# SCH.net
KiCad netlist of a schematic drawn in EAGLE
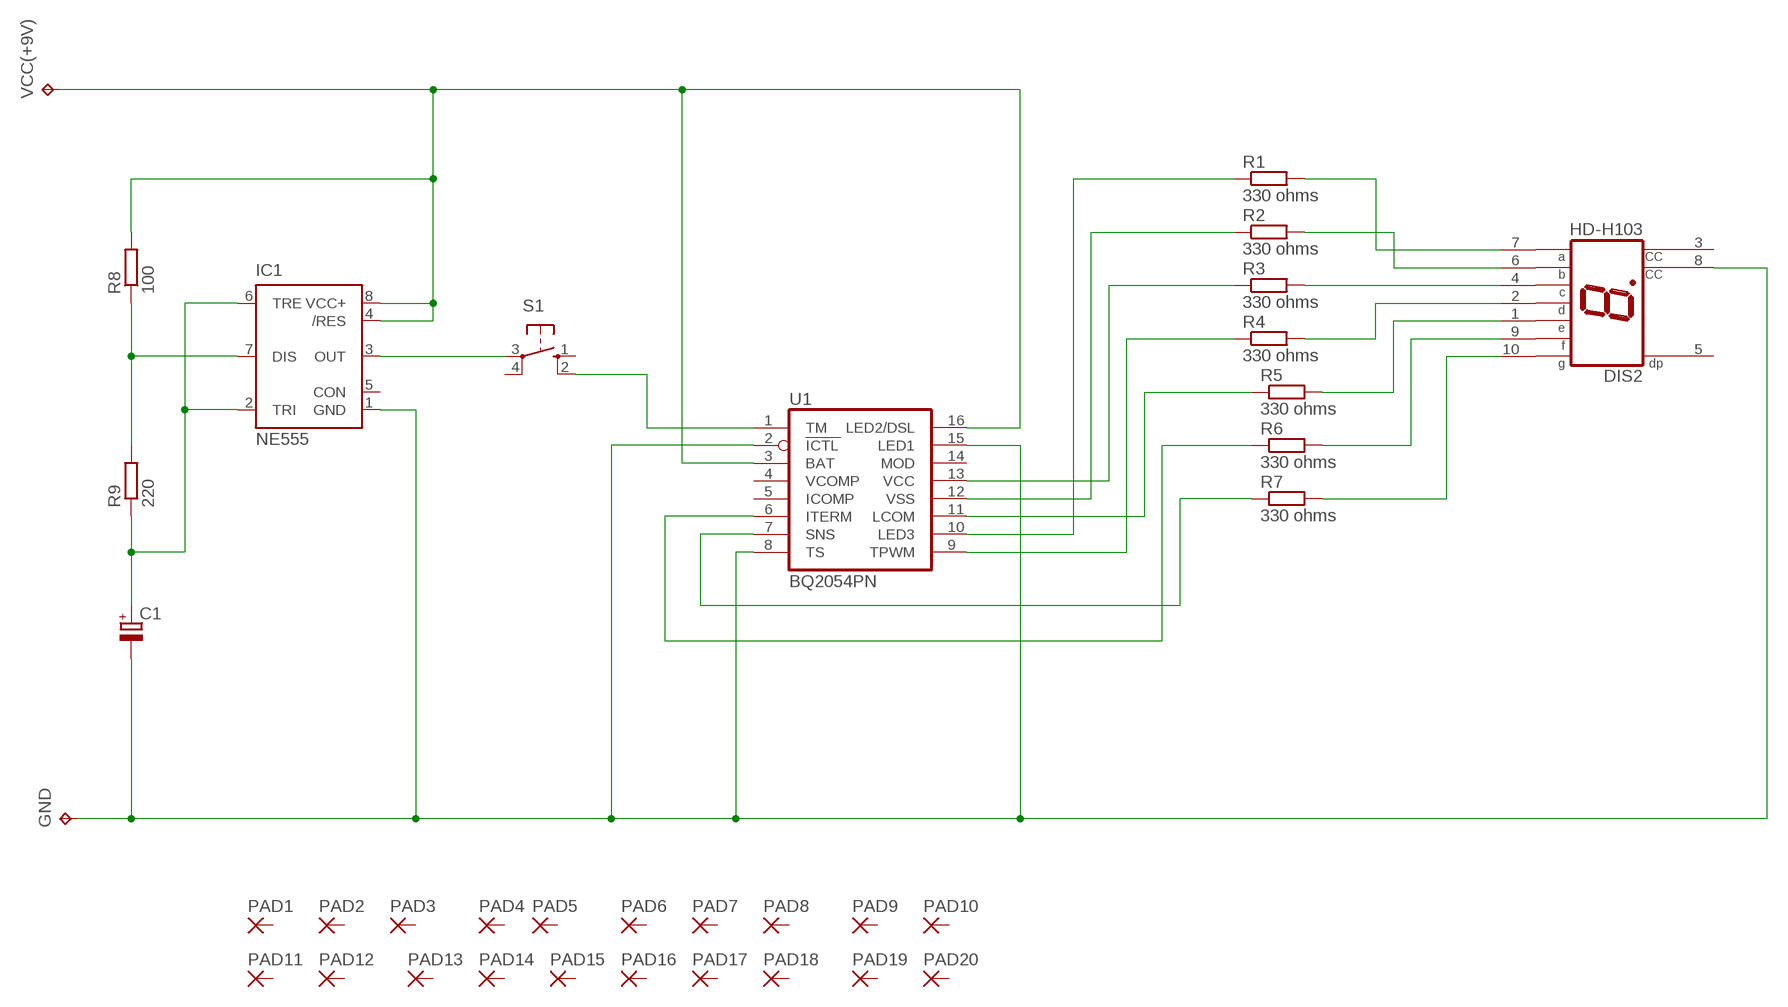
[diagram p0: schematic, sheet 1]

(export (version "E")
  (design (tool "Eeschema 10.0.6"))
  (components
    (comp (ref "C1")
      (value "CPOL-EUB45181B")
      (footprint "eagle-import:B45181B")
      (libsource (lib "eagle-import") (part "CPOL-EUB45181B"))
    )
    (comp (ref "DIS2")
      (value "HD-H103")
      (footprint "eagle-import:HDSP-M")
      (libsource (lib "eagle-import") (part "HD-H103"))
    )
    (comp (ref "GND")
      (value "TPPAD1-13Y")
      (footprint "eagle-import:P1-13Y")
      (libsource (lib "eagle-import") (part "TPPAD1-13Y"))
    )
    (comp (ref "IC1")
      (value "NE555")
      (footprint "eagle-import:DIL-08")
      (fields (field (name "MF") "Arrow Electronics") (field (name "MPN") "NE555N"))
      (libsource (lib "eagle-import") (part "NE555"))
    )
    (comp (ref "PAD1")
      (value "2,54/0,8")
      (footprint "eagle-import:2,54_0,8")
      (libsource (lib "eagle-import") (part "2,54/0,8"))
    )
    (comp (ref "PAD2")
      (value "2,54/0,8")
      (footprint "eagle-import:2,54_0,8")
      (libsource (lib "eagle-import") (part "2,54/0,8"))
    )
    (comp (ref "PAD3")
      (value "2,54/0,8")
      (footprint "eagle-import:2,54_0,8")
      (libsource (lib "eagle-import") (part "2,54/0,8"))
    )
    (comp (ref "PAD4")
      (value "2,54/0,8")
      (footprint "eagle-import:2,54_0,8")
      (libsource (lib "eagle-import") (part "2,54/0,8"))
    )
    (comp (ref "PAD5")
      (value "2,54/0,8")
      (footprint "eagle-import:2,54_0,8")
      (libsource (lib "eagle-import") (part "2,54/0,8"))
    )
    (comp (ref "PAD6")
      (value "2,54/0,8")
      (footprint "eagle-import:2,54_0,8")
      (libsource (lib "eagle-import") (part "2,54/0,8"))
    )
    (comp (ref "PAD7")
      (value "2,54/0,8")
      (footprint "eagle-import:2,54_0,8")
      (libsource (lib "eagle-import") (part "2,54/0,8"))
    )
    (comp (ref "PAD8")
      (value "2,54/0,8")
      (footprint "eagle-import:2,54_0,8")
      (libsource (lib "eagle-import") (part "2,54/0,8"))
    )
    (comp (ref "PAD9")
      (value "2,54/0,8")
      (footprint "eagle-import:2,54_0,8")
      (libsource (lib "eagle-import") (part "2,54/0,8"))
    )
    (comp (ref "PAD10")
      (value "2,54/0,8")
      (footprint "eagle-import:2,54_0,8")
      (libsource (lib "eagle-import") (part "2,54/0,8"))
    )
    (comp (ref "PAD11")
      (value "2,54/0,8")
      (footprint "eagle-import:2,54_0,8")
      (libsource (lib "eagle-import") (part "2,54/0,8"))
    )
    (comp (ref "PAD12")
      (value "2,54/0,8")
      (footprint "eagle-import:2,54_0,8")
      (libsource (lib "eagle-import") (part "2,54/0,8"))
    )
    (comp (ref "PAD13")
      (value "2,54/0,8")
      (footprint "eagle-import:2,54_0,8")
      (libsource (lib "eagle-import") (part "2,54/0,8"))
    )
    (comp (ref "PAD14")
      (value "2,54/0,8")
      (footprint "eagle-import:2,54_0,8")
      (libsource (lib "eagle-import") (part "2,54/0,8"))
    )
    (comp (ref "PAD15")
      (value "2,54/0,8")
      (footprint "eagle-import:2,54_0,8")
      (libsource (lib "eagle-import") (part "2,54/0,8"))
    )
    (comp (ref "PAD16")
      (value "2,54/0,8")
      (footprint "eagle-import:2,54_0,8")
      (libsource (lib "eagle-import") (part "2,54/0,8"))
    )
    (comp (ref "PAD17")
      (value "2,54/0,8")
      (footprint "eagle-import:2,54_0,8")
      (libsource (lib "eagle-import") (part "2,54/0,8"))
    )
    (comp (ref "PAD18")
      (value "2,54/0,8")
      (footprint "eagle-import:2,54_0,8")
      (libsource (lib "eagle-import") (part "2,54/0,8"))
    )
    (comp (ref "PAD19")
      (value "2,54/0,8")
      (footprint "eagle-import:2,54_0,8")
      (libsource (lib "eagle-import") (part "2,54/0,8"))
    )
    (comp (ref "PAD20")
      (value "2,54/0,8")
      (footprint "eagle-import:2,54_0,8")
      (libsource (lib "eagle-import") (part "2,54/0,8"))
    )
    (comp (ref "R1")
      (value "330 ohms")
      (footprint "eagle-import:0207_10")
      (libsource (lib "eagle-import") (part "R-EU_0207/10"))
    )
    (comp (ref "R2")
      (value "330 ohms")
      (footprint "eagle-import:0207_10")
      (libsource (lib "eagle-import") (part "R-EU_0207/10"))
    )
    (comp (ref "R3")
      (value "330 ohms")
      (footprint "eagle-import:0207_10")
      (libsource (lib "eagle-import") (part "R-EU_0207/10"))
    )
    (comp (ref "R4")
      (value "330 ohms")
      (footprint "eagle-import:0207_10")
      (libsource (lib "eagle-import") (part "R-EU_0207/10"))
    )
    (comp (ref "R5")
      (value "330 ohms")
      (footprint "eagle-import:0207_10")
      (libsource (lib "eagle-import") (part "R-EU_0207/10"))
    )
    (comp (ref "R6")
      (value "330 ohms")
      (footprint "eagle-import:0207_10")
      (libsource (lib "eagle-import") (part "R-EU_0207/10"))
    )
    (comp (ref "R7")
      (value "330 ohms")
      (footprint "eagle-import:0207_10")
      (libsource (lib "eagle-import") (part "R-EU_0207/10"))
    )
    (comp (ref "R8")
      (value "100")
      (footprint "eagle-import:0207_10")
      (libsource (lib "eagle-import") (part "R-EU_0207/10"))
    )
    (comp (ref "R9")
      (value "220")
      (footprint "eagle-import:0207_10")
      (libsource (lib "eagle-import") (part "R-EU_0207/10"))
    )
    (comp (ref "S1")
      (value "40-XX")
      (footprint "eagle-import:B3F-40XX")
      (fields (field (name "MF") "OMRON COMPONENTS USA") (field (name "MPN") "B3F-4000"))
      (libsource (lib "eagle-import") (part "40-XX"))
    )
    (comp (ref "U1")
      (value "BQ2054PN")
      (footprint "eagle-import:DIL16")
      (fields (field (name "MF") "TEXAS INSTRUMENT CONNECTORS"))
      (libsource (lib "eagle-import") (part "BQ2054PN"))
    )
    (comp (ref "VCC(+9V)")
      (value "TPPAD1-13Y")
      (footprint "eagle-import:P1-13Y")
      (libsource (lib "eagle-import") (part "TPPAD1-13Y"))
    )
  )
  (nets
    (net (code "1") (name "Net-(DIS2-A)") (class "Default")
      (node (ref "DIS2") (pin "7") (pinfunction "A_7") (pintype "passive"))
      (node (ref "R1") (pin "2") (pinfunction "2_2") (pintype "passive"))
    )
    (net (code "2") (name "Net-(DIS2-B)") (class "Default")
      (node (ref "DIS2") (pin "6") (pinfunction "B_6") (pintype "passive"))
      (node (ref "R2") (pin "2") (pinfunction "2_2") (pintype "passive"))
    )
    (net (code "3") (name "Net-(DIS2-C)") (class "Default")
      (node (ref "DIS2") (pin "4") (pinfunction "C_4") (pintype "passive"))
      (node (ref "R3") (pin "2") (pinfunction "2_2") (pintype "passive"))
    )
    (net (code "4") (name "Net-(DIS2-D)") (class "Default")
      (node (ref "DIS2") (pin "2") (pinfunction "D_2") (pintype "passive"))
      (node (ref "R4") (pin "2") (pinfunction "2_2") (pintype "passive"))
    )
    (net (code "5") (name "Net-(DIS2-E)") (class "Default")
      (node (ref "DIS2") (pin "1") (pinfunction "E_1") (pintype "passive"))
      (node (ref "R5") (pin "2") (pinfunction "2_2") (pintype "passive"))
    )
    (net (code "6") (name "Net-(DIS2-F)") (class "Default")
      (node (ref "DIS2") (pin "9") (pinfunction "F_9") (pintype "passive"))
      (node (ref "R6") (pin "2") (pinfunction "2_2") (pintype "passive"))
    )
    (net (code "7") (name "Net-(DIS2-G)") (class "Default")
      (node (ref "DIS2") (pin "10") (pinfunction "G_10") (pintype "passive"))
      (node (ref "R7") (pin "2") (pinfunction "2_2") (pintype "passive"))
    )
    (net (code "8") (name "Net-(IC1-DIS)") (class "Default")
      (node (ref "IC1") (pin "7") (pinfunction "DIS_7") (pintype "input"))
      (node (ref "R8") (pin "1") (pinfunction "1_1") (pintype "passive"))
      (node (ref "R9") (pin "2") (pinfunction "2_2") (pintype "passive"))
    )
    (net (code "9") (name "Net-(IC1-GND)") (class "Default")
      (node (ref "C1") (pin "-") (pinfunction "-_-") (pintype "passive"))
      (node (ref "DIS2") (pin "8") (pinfunction "CC_8") (pintype "passive"))
      (node (ref "GND") (pin "TP") (pinfunction "TP_TP") (pintype "input"))
      (node (ref "IC1") (pin "1") (pinfunction "GND_1") (pintype "power_in"))
      (node (ref "U1") (pin "15") (pinfunction "LED1_15") (pintype "tri_state"))
      (node (ref "U1") (pin "2") (pinfunction "ICTL_2") (pintype "output"))
      (node (ref "U1") (pin "8") (pinfunction "TS_8") (pintype "input"))
    )
    (net (code "10") (name "Net-(IC1-OUT)") (class "Default")
      (node (ref "IC1") (pin "3") (pinfunction "OUT_3") (pintype "output"))
      (node (ref "S1") (pin "3") (pinfunction "P_3") (pintype "passive"))
    )
    (net (code "11") (name "Net-(IC1-TRE)") (class "Default")
      (node (ref "C1") (pin "+") (pinfunction "+_+") (pintype "passive"))
      (node (ref "IC1") (pin "2") (pinfunction "TRI_2") (pintype "input"))
      (node (ref "IC1") (pin "6") (pinfunction "TRE_6") (pintype "input"))
      (node (ref "R9") (pin "1") (pinfunction "1_1") (pintype "passive"))
    )
    (net (code "12") (name "Net-(IC1-VCC+)") (class "Default")
      (node (ref "IC1") (pin "4") (pinfunction "/RES_4") (pintype "input"))
      (node (ref "IC1") (pin "8") (pinfunction "VCC+_8") (pintype "power_in"))
      (node (ref "R8") (pin "2") (pinfunction "2_2") (pintype "passive"))
      (node (ref "U1") (pin "16") (pinfunction "LED2/DSL_16") (pintype "tri_state"))
      (node (ref "U1") (pin "3") (pinfunction "BAT_3") (pintype "input"))
      (node (ref "VCC(+9V)") (pin "TP") (pinfunction "TP_TP") (pintype "input"))
    )
    (net (code "13") (name "Net-(S1-S1)") (class "Default")
      (node (ref "S1") (pin "2") (pinfunction "S1_2") (pintype "passive"))
      (node (ref "U1") (pin "1") (pinfunction "TM_1") (pintype "input"))
    )
    (net (code "14") (name "Net-(U1-ITERM)") (class "Default")
      (node (ref "R6") (pin "1") (pinfunction "1_1") (pintype "passive"))
      (node (ref "U1") (pin "6") (pinfunction "ITERM_6") (pintype "input"))
    )
    (net (code "15") (name "Net-(U1-LCOM)") (class "Default")
      (node (ref "R5") (pin "1") (pinfunction "1_1") (pintype "passive"))
      (node (ref "U1") (pin "11") (pinfunction "LCOM_11") (pintype "output"))
    )
    (net (code "16") (name "Net-(U1-LED3)") (class "Default")
      (node (ref "R1") (pin "1") (pinfunction "1_1") (pintype "passive"))
      (node (ref "U1") (pin "10") (pinfunction "LED3_10") (pintype "tri_state"))
    )
    (net (code "17") (name "Net-(U1-SNS)") (class "Default")
      (node (ref "R7") (pin "1") (pinfunction "1_1") (pintype "passive"))
      (node (ref "U1") (pin "7") (pinfunction "SNS_7") (pintype "input"))
    )
    (net (code "18") (name "Net-(U1-TPWM)") (class "Default")
      (node (ref "R4") (pin "1") (pinfunction "1_1") (pintype "passive"))
      (node (ref "U1") (pin "9") (pinfunction "TPWM_9") (pintype "input"))
    )
    (net (code "19") (name "Net-(U1-VCC)") (class "Default")
      (node (ref "R3") (pin "1") (pinfunction "1_1") (pintype "passive"))
      (node (ref "U1") (pin "13") (pinfunction "VCC_13") (pintype "power_in"))
    )
    (net (code "20") (name "Net-(U1-VSS)") (class "Default")
      (node (ref "R2") (pin "1") (pinfunction "1_1") (pintype "passive"))
      (node (ref "U1") (pin "12") (pinfunction "VSS_12") (pintype "power_in"))
    )
    (net (code "21") (name "unconnected-(DIS2-CC-Pad3)") (class "Default")
      (node (ref "DIS2") (pin "3") (pinfunction "CC_3") (pintype "passive"))
    )
    (net (code "22") (name "unconnected-(DIS2-DP-Pad5)") (class "Default")
      (node (ref "DIS2") (pin "5") (pinfunction "DP_5") (pintype "passive"))
    )
    (net (code "23") (name "unconnected-(IC1-CON-Pad5)") (class "Default")
      (node (ref "IC1") (pin "5") (pinfunction "CON_5") (pintype "input"))
    )
    (net (code "24") (name "unconnected-(PAD1-P-Pad1)") (class "Default")
      (node (ref "PAD1") (pin "1") (pinfunction "P_1") (pintype "passive"))
    )
    (net (code "25") (name "unconnected-(PAD2-P-Pad1)") (class "Default")
      (node (ref "PAD2") (pin "1") (pinfunction "P_1") (pintype "passive"))
    )
    (net (code "26") (name "unconnected-(PAD3-P-Pad1)") (class "Default")
      (node (ref "PAD3") (pin "1") (pinfunction "P_1") (pintype "passive"))
    )
    (net (code "27") (name "unconnected-(PAD4-P-Pad1)") (class "Default")
      (node (ref "PAD4") (pin "1") (pinfunction "P_1") (pintype "passive"))
    )
    (net (code "28") (name "unconnected-(PAD5-P-Pad1)") (class "Default")
      (node (ref "PAD5") (pin "1") (pinfunction "P_1") (pintype "passive"))
    )
    (net (code "29") (name "unconnected-(PAD6-P-Pad1)") (class "Default")
      (node (ref "PAD6") (pin "1") (pinfunction "P_1") (pintype "passive"))
    )
    (net (code "30") (name "unconnected-(PAD7-P-Pad1)") (class "Default")
      (node (ref "PAD7") (pin "1") (pinfunction "P_1") (pintype "passive"))
    )
    (net (code "31") (name "unconnected-(PAD8-P-Pad1)") (class "Default")
      (node (ref "PAD8") (pin "1") (pinfunction "P_1") (pintype "passive"))
    )
    (net (code "32") (name "unconnected-(PAD9-P-Pad1)") (class "Default")
      (node (ref "PAD9") (pin "1") (pinfunction "P_1") (pintype "passive"))
    )
    (net (code "33") (name "unconnected-(PAD10-P-Pad1)") (class "Default")
      (node (ref "PAD10") (pin "1") (pinfunction "P_1") (pintype "passive"))
    )
    (net (code "34") (name "unconnected-(PAD11-P-Pad1)") (class "Default")
      (node (ref "PAD11") (pin "1") (pinfunction "P_1") (pintype "passive"))
    )
    (net (code "35") (name "unconnected-(PAD12-P-Pad1)") (class "Default")
      (node (ref "PAD12") (pin "1") (pinfunction "P_1") (pintype "passive"))
    )
    (net (code "36") (name "unconnected-(PAD13-P-Pad1)") (class "Default")
      (node (ref "PAD13") (pin "1") (pinfunction "P_1") (pintype "passive"))
    )
    (net (code "37") (name "unconnected-(PAD14-P-Pad1)") (class "Default")
      (node (ref "PAD14") (pin "1") (pinfunction "P_1") (pintype "passive"))
    )
    (net (code "38") (name "unconnected-(PAD15-P-Pad1)") (class "Default")
      (node (ref "PAD15") (pin "1") (pinfunction "P_1") (pintype "passive"))
    )
    (net (code "39") (name "unconnected-(PAD16-P-Pad1)") (class "Default")
      (node (ref "PAD16") (pin "1") (pinfunction "P_1") (pintype "passive"))
    )
    (net (code "40") (name "unconnected-(PAD17-P-Pad1)") (class "Default")
      (node (ref "PAD17") (pin "1") (pinfunction "P_1") (pintype "passive"))
    )
    (net (code "41") (name "unconnected-(PAD18-P-Pad1)") (class "Default")
      (node (ref "PAD18") (pin "1") (pinfunction "P_1") (pintype "passive"))
    )
    (net (code "42") (name "unconnected-(PAD19-P-Pad1)") (class "Default")
      (node (ref "PAD19") (pin "1") (pinfunction "P_1") (pintype "passive"))
    )
    (net (code "43") (name "unconnected-(PAD20-P-Pad1)") (class "Default")
      (node (ref "PAD20") (pin "1") (pinfunction "P_1") (pintype "passive"))
    )
    (net (code "44") (name "unconnected-(S1-P1-Pad4)") (class "Default")
      (node (ref "S1") (pin "4") (pinfunction "P1_4") (pintype "passive"))
    )
    (net (code "45") (name "unconnected-(S1-S-Pad1)") (class "Default")
      (node (ref "S1") (pin "1") (pinfunction "S_1") (pintype "passive"))
    )
    (net (code "46") (name "unconnected-(U1-ICOMP-Pad5)") (class "Default")
      (node (ref "U1") (pin "5") (pinfunction "ICOMP_5") (pintype "input"))
    )
    (net (code "47") (name "unconnected-(U1-MOD-Pad14)") (class "Default")
      (node (ref "U1") (pin "14") (pinfunction "MOD_14") (pintype "output"))
    )
    (net (code "48") (name "unconnected-(U1-VCOMP-Pad4)") (class "Default")
      (node (ref "U1") (pin "4") (pinfunction "VCOMP_4") (pintype "input"))
    )
  )
)
